# dcb_lite_logic.net
KiCad netlist of a schematic drawn in Altium Designer
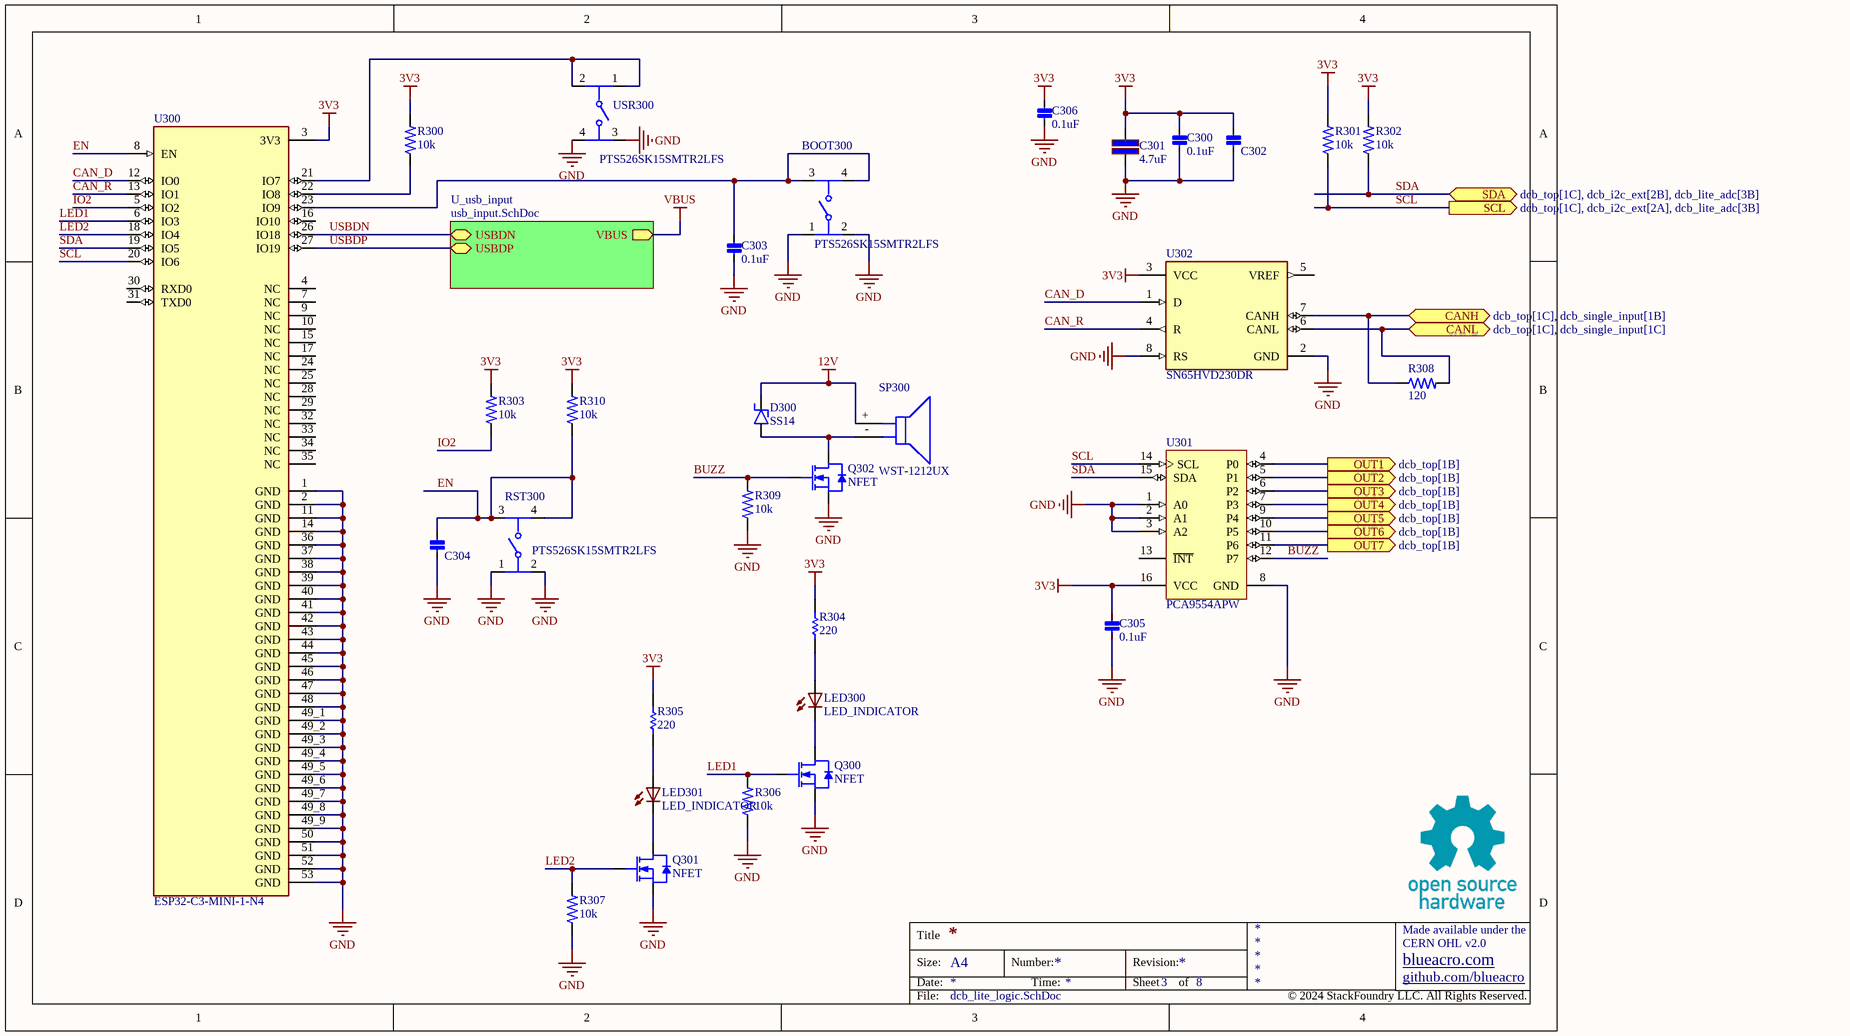
[diagram p0: dcb_lite_logic.SchDoc]

(export (version "E")
  (design (tool "Eeschema 10.0.6"))
  (components
    (comp (ref "BOOT300")
      (value "PTS526SK15SMTR2LFS")
      (footprint "FP-PTS526SK15SMTR2LFS-MFG")
      (description "Switch Tactile N.O. SPST Round Button Gull Wing 0.05A 12VDC 200000Cycles 2.45N SMD T/R")
      (libsource (lib "StackFoundry LLC") (part "b8895f3f4cefb76e1819d2863dba89b"))
    )
    (comp (ref "C300")
      (value "0.1uF")
      (footprint "FP-CL10-IPC_B")
      (description "Cap Ceramic 0.1uF 50V X7R 20% SMD 0603 125C Paper T/R")
      (fields (field (name "VOLTAGE") "50V") (field (name "Comment") "CAP 0.1uF 50V X7R 0603"))
      (libsource (lib "StackFoundry LLC") (part "C-EU"))
    )
    (comp (ref "C301")
      (value "4.7uF")
      (footprint "CAPC3225X20N")
      (description "CAP CER 4.7UF 50V X7R 1210")
      (fields (field (name "VOLTAGE") "50V") (field (name "TOLERANCE") "10%"))
      (libsource (lib "StackFoundry LLC") (part "4.7uF"))
    )
    (comp (ref "C302")
      (value "CAP 1uF 10V X7R 0603")
      (footprint "FP-CL10-IPC_B")
      (description "Cap Ceramic 1uF 10V X7R 10% SMD 0603 125C Paper T/R")
      (libsource (lib "StackFoundry LLC") (part "C-EU"))
    )
    (comp (ref "C303")
      (value "0.1uF")
      (footprint "FP-CL10-IPC_B")
      (description "Cap Ceramic 0.1uF 50V X7R 20% SMD 0603 125C Paper T/R")
      (fields (field (name "VOLTAGE") "50V") (field (name "Comment") "CAP 0.1uF 50V X7R 0603"))
      (libsource (lib "StackFoundry LLC") (part "C-EU"))
    )
    (comp (ref "C304")
      (value "CAP 1uF 10V X7R 0603")
      (footprint "FP-CL10-IPC_B")
      (description "Cap Ceramic 1uF 10V X7R 10% SMD 0603 125C Paper T/R")
      (libsource (lib "StackFoundry LLC") (part "C-EU"))
    )
    (comp (ref "C305")
      (value "0.1uF")
      (footprint "FP-CL10-IPC_B")
      (description "Cap Ceramic 0.1uF 50V X7R 20% SMD 0603 125C Paper T/R")
      (fields (field (name "VOLTAGE") "50V") (field (name "Comment") "CAP 0.1uF 50V X7R 0603"))
      (libsource (lib "StackFoundry LLC") (part "C-EU"))
    )
    (comp (ref "C306")
      (value "0.1uF")
      (footprint "FP-CL10-IPC_B")
      (description "Cap Ceramic 0.1uF 50V X7R 20% SMD 0603 125C Paper T/R")
      (fields (field (name "VOLTAGE") "50V") (field (name "Comment") "CAP 0.1uF 50V X7R 0603"))
      (libsource (lib "StackFoundry LLC") (part "C-EU"))
    )
    (comp (ref "D300")
      (value "SS14")
      (footprint "SMA")
      (libsource (lib "StackFoundry LLC") (part "DIODE_SCHOTTKY"))
    )
    (comp (ref "LED300")
      (value "LED_INDICATOR")
      (footprint "LED5MM")
      (libsource (lib "StackFoundry LLC") (part "LED_INDICATOR"))
    )
    (comp (ref "LED301")
      (value "LED_INDICATOR")
      (footprint "LED5MM")
      (libsource (lib "StackFoundry LLC") (part "LED_INDICATOR"))
    )
    (comp (ref "Q300")
      (value "NFET")
      (footprint "SOT23-3")
      (libsource (lib "StackFoundry LLC") (part "NFET"))
    )
    (comp (ref "Q301")
      (value "NFET")
      (footprint "SOT23-3")
      (libsource (lib "StackFoundry LLC") (part "NFET"))
    )
    (comp (ref "Q302")
      (value "NFET")
      (footprint "SOT23-3")
      (libsource (lib "StackFoundry LLC") (part "NFET"))
    )
    (comp (ref "R300")
      (value "10k")
      (footprint "RESC1608-IPC-ML")
      (description "Res General Purpose Thick Film 0603 10K Ohm 1% 1/10W ±100ppm/°C Molded SMD Paper T/R")
      (fields (field (name "Comment") "10K 0603 1%"))
      (libsource (lib "StackFoundry LLC") (part "R-US"))
    )
    (comp (ref "R301")
      (value "10k")
      (footprint "RESC1608-IPC-ML")
      (description "Res General Purpose Thick Film 0603 10K Ohm 1% 1/10W ±100ppm/°C Molded SMD Paper T/R")
      (fields (field (name "Comment") "10K 0603 1%"))
      (libsource (lib "StackFoundry LLC") (part "R-US"))
    )
    (comp (ref "R302")
      (value "10k")
      (footprint "RESC1608-IPC-ML")
      (description "Res General Purpose Thick Film 0603 10K Ohm 1% 1/10W ±100ppm/°C Molded SMD Paper T/R")
      (fields (field (name "Comment") "10K 0603 1%"))
      (libsource (lib "StackFoundry LLC") (part "R-US"))
    )
    (comp (ref "R303")
      (value "10k")
      (footprint "RESC1608-IPC-ML")
      (description "Res General Purpose Thick Film 0603 10K Ohm 1% 1/10W ±100ppm/°C Molded SMD Paper T/R")
      (fields (field (name "Comment") "10K 0603 1%"))
      (libsource (lib "StackFoundry LLC") (part "R-US"))
    )
    (comp (ref "R304")
      (value "220")
      (footprint "RESC1608-IPC-ML")
      (fields (field (name "TOLERANCE") "5%") (field (name "Comment") "220R 0603 5%"))
      (libsource (lib "StackFoundry LLC") (part "RES-2"))
    )
    (comp (ref "R305")
      (value "220")
      (footprint "RESC1608-IPC-ML")
      (fields (field (name "TOLERANCE") "5%") (field (name "Comment") "220R 0603 5%"))
      (libsource (lib "StackFoundry LLC") (part "RES-2"))
    )
    (comp (ref "R306")
      (value "10k")
      (footprint "RESC1608-IPC-ML")
      (description "Res General Purpose Thick Film 0603 10K Ohm 1% 1/10W ±100ppm/°C Molded SMD Paper T/R")
      (fields (field (name "Comment") "10K 0603 1%"))
      (libsource (lib "StackFoundry LLC") (part "R-US"))
    )
    (comp (ref "R307")
      (value "10k")
      (footprint "RESC1608-IPC-ML")
      (description "Res General Purpose Thick Film 0603 10K Ohm 1% 1/10W ±100ppm/°C Molded SMD Paper T/R")
      (fields (field (name "Comment") "10K 0603 1%"))
      (libsource (lib "StackFoundry LLC") (part "R-US"))
    )
    (comp (ref "R308")
      (value "120")
      (footprint "RESC1608-IPC-ML")
      (description "120R 0.1W 5% 0603 (1608 Metric)  SMD")
      (fields (field (name "TOLERANCE") "5%") (field (name "POWER") "100mW"))
      (libsource (lib "StackFoundry LLC") (part "R-US"))
    )
    (comp (ref "R309")
      (value "10k")
      (footprint "RESC1608-IPC-ML")
      (description "Res General Purpose Thick Film 0603 10K Ohm 1% 1/10W ±100ppm/°C Molded SMD Paper T/R")
      (fields (field (name "Comment") "10K 0603 1%"))
      (libsource (lib "StackFoundry LLC") (part "R-US"))
    )
    (comp (ref "R310")
      (value "10k")
      (footprint "RESC1608-IPC-ML")
      (description "Res General Purpose Thick Film 0603 10K Ohm 1% 1/10W ±100ppm/°C Molded SMD Paper T/R")
      (fields (field (name "Comment") "10K 0603 1%"))
      (libsource (lib "StackFoundry LLC") (part "R-US"))
    )
    (comp (ref "RST300")
      (value "PTS526SK15SMTR2LFS")
      (footprint "FP-PTS526SK15SMTR2LFS-MFG")
      (description "Switch Tactile N.O. SPST Round Button Gull Wing 0.05A 12VDC 200000Cycles 2.45N SMD T/R")
      (libsource (lib "StackFoundry LLC") (part "b8895f3f4cefb76e1819d2863dba89b"))
    )
    (comp (ref "SP300")
      (value "WST-1212UX")
      (footprint "WST-1212UX-Footprint-1")
      (description "Audio Magnetic Xdcr 9-15V Th")
      (libsource (lib "StackFoundry LLC") (part "WST-1212UX-Symbol-1"))
    )
    (comp (ref "U300")
      (value "ESP32-C3-MINI-1-N4")
      (footprint "XCVR_ESP32-C3-MINI-1-N4")
      (fields (field (name "MF") "Espressif Systems"))
      (libsource (lib "StackFoundry LLC") (part "ESP32-C3-MINI-1-N4"))
    )
    (comp (ref "U301")
      (value "PCA9554APW")
      (footprint "PW0016A_L")
      (description "I2C/SMBus Interface 100kHz/400kHz 5.5V 16-Pin TSSOP Tube / IC I/O EXPANDER I2C 8B 16TSSOP")
      (libsource (lib "StackFoundry LLC") (part "TI-PCA9554A-TSSOP_PW-16"))
    )
    (comp (ref "U302")
      (value "SN65HVD230DR")
      (footprint "FP-D0008A-IPC_B")
      (description "EAR99 65HVD230 Cut Tape (CT) CANbus interface driver 3.3V 17mA 72.603129mg 1Mbps")
      (libsource (lib "StackFoundry LLC") (part "43b56812b1adf0e60a7acfb7c27ab91"))
    )
    (comp (ref "USR300")
      (value "PTS526SK15SMTR2LFS")
      (footprint "FP-PTS526SK15SMTR2LFS-MFG")
      (description "Switch Tactile N.O. SPST Round Button Gull Wing 0.05A 12VDC 200000Cycles 2.45N SMD T/R")
      (libsource (lib "StackFoundry LLC") (part "b8895f3f4cefb76e1819d2863dba89b"))
    )
  )
  (nets
    (net (code "1") (name "/BUZZ") (class "Default")
      (node (ref "Q302") (pin "1") (pinfunction "G_1") (pintype "passive"))
      (node (ref "R309") (pin "2") (pinfunction "2_2") (pintype "passive"))
      (node (ref "U301") (pin "12") (pinfunction "P7_12") (pintype "bidirectional"))
    )
    (net (code "2") (name "/CANH") (class "Default")
      (node (ref "R308") (pin "1") (pinfunction "1_1") (pintype "passive"))
      (node (ref "U302") (pin "7") (pinfunction "CANH_7") (pintype "bidirectional"))
    )
    (net (code "3") (name "/CANL") (class "Default")
      (node (ref "R308") (pin "2") (pinfunction "2_2") (pintype "passive"))
      (node (ref "U302") (pin "6") (pinfunction "CANL_6") (pintype "bidirectional"))
    )
    (net (code "4") (name "/CAN_D") (class "Default")
      (node (ref "U300") (pin "12") (pinfunction "IO0_12") (pintype "bidirectional"))
      (node (ref "U302") (pin "1") (pinfunction "D_1") (pintype "input"))
    )
    (net (code "5") (name "/CAN_R") (class "Default")
      (node (ref "U300") (pin "13") (pinfunction "IO1_13") (pintype "bidirectional"))
      (node (ref "U302") (pin "4") (pinfunction "R_4") (pintype "output"))
    )
    (net (code "6") (name "/EN") (class "Default")
      (node (ref "C304") (pin "1") (pinfunction "1_1") (pintype "passive"))
      (node (ref "R310") (pin "1") (pinfunction "1_1") (pintype "passive"))
      (node (ref "RST300") (pin "3") (pinfunction "3_3") (pintype "passive"))
      (node (ref "RST300") (pin "4") (pinfunction "4_4") (pintype "passive"))
      (node (ref "U300") (pin "8") (pinfunction "EN_8") (pintype "input"))
    )
    (net (code "7") (name "/IO2") (class "Default")
      (node (ref "R303") (pin "1") (pinfunction "1_1") (pintype "passive"))
      (node (ref "U300") (pin "5") (pinfunction "IO2_5") (pintype "bidirectional"))
    )
    (net (code "8") (name "/LED1") (class "Default")
      (node (ref "Q300") (pin "1") (pinfunction "G_1") (pintype "passive"))
      (node (ref "R306") (pin "2") (pinfunction "2_2") (pintype "passive"))
      (node (ref "U300") (pin "6") (pinfunction "IO3_6") (pintype "bidirectional"))
    )
    (net (code "9") (name "/LED2") (class "Default")
      (node (ref "Q301") (pin "1") (pinfunction "G_1") (pintype "passive"))
      (node (ref "R307") (pin "2") (pinfunction "2_2") (pintype "passive"))
      (node (ref "U300") (pin "18") (pinfunction "IO4_18") (pintype "bidirectional"))
    )
    (net (code "10") (name "/OUT1") (class "Default")
      (node (ref "U301") (pin "4") (pinfunction "P0_4") (pintype "bidirectional"))
    )
    (net (code "11") (name "/OUT2") (class "Default")
      (node (ref "U301") (pin "5") (pinfunction "P1_5") (pintype "bidirectional"))
    )
    (net (code "12") (name "/OUT3") (class "Default")
      (node (ref "U301") (pin "6") (pinfunction "P2_6") (pintype "bidirectional"))
    )
    (net (code "13") (name "/OUT4") (class "Default")
      (node (ref "U301") (pin "7") (pinfunction "P3_7") (pintype "bidirectional"))
    )
    (net (code "14") (name "/OUT5") (class "Default")
      (node (ref "U301") (pin "9") (pinfunction "P4_9") (pintype "bidirectional"))
    )
    (net (code "15") (name "/OUT6") (class "Default")
      (node (ref "U301") (pin "10") (pinfunction "P5_10") (pintype "bidirectional"))
    )
    (net (code "16") (name "/OUT7") (class "Default")
      (node (ref "U301") (pin "11") (pinfunction "P6_11") (pintype "bidirectional"))
    )
    (net (code "17") (name "/SCL") (class "Default")
      (node (ref "R301") (pin "1") (pinfunction "1_1") (pintype "passive"))
      (node (ref "U300") (pin "20") (pinfunction "IO6_20") (pintype "bidirectional"))
      (node (ref "U301") (pin "14") (pinfunction "SCL_14") (pintype "input"))
    )
    (net (code "18") (name "/SDA") (class "Default")
      (node (ref "R302") (pin "1") (pinfunction "1_1") (pintype "passive"))
      (node (ref "U300") (pin "19") (pinfunction "IO5_19") (pintype "bidirectional"))
      (node (ref "U301") (pin "15") (pinfunction "SDA_15") (pintype "bidirectional"))
    )
    (net (code "19") (name "/USBDN") (class "Default")
      (node (ref "U300") (pin "26") (pinfunction "IO18_26") (pintype "bidirectional"))
    )
    (net (code "20") (name "/USBDP") (class "Default")
      (node (ref "U300") (pin "27") (pinfunction "IO19_27") (pintype "bidirectional"))
    )
    (net (code "21") (name "3V3") (class "Default")
      (node (ref "C300") (pin "1") (pinfunction "1_1") (pintype "passive"))
      (node (ref "C301") (pin "2") (pintype "passive"))
      (node (ref "C302") (pin "1") (pinfunction "1_1") (pintype "passive"))
      (node (ref "C305") (pin "1") (pinfunction "1_1") (pintype "passive"))
      (node (ref "C306") (pin "1") (pinfunction "1_1") (pintype "passive"))
      (node (ref "R300") (pin "2") (pinfunction "2_2") (pintype "passive"))
      (node (ref "R301") (pin "2") (pinfunction "2_2") (pintype "passive"))
      (node (ref "R302") (pin "2") (pinfunction "2_2") (pintype "passive"))
      (node (ref "R303") (pin "2") (pinfunction "2_2") (pintype "passive"))
      (node (ref "R304") (pin "2") (pinfunction "2_2") (pintype "passive"))
      (node (ref "R305") (pin "2") (pinfunction "2_2") (pintype "passive"))
      (node (ref "R310") (pin "2") (pinfunction "2_2") (pintype "passive"))
      (node (ref "U300") (pin "3") (pinfunction "3V3_3") (pintype "power_in"))
      (node (ref "U301") (pin "16") (pinfunction "VCC_16") (pintype "power_in"))
      (node (ref "U302") (pin "3") (pinfunction "VCC_3") (pintype "power_in"))
    )
    (net (code "22") (name "12V") (class "Default")
      (node (ref "D300") (pin "K") (pinfunction "K_K") (pintype "power_in"))
      (node (ref "SP300") (pin "+") (pinfunction "+_+") (pintype "passive"))
    )
    (net (code "23") (name "GND") (class "Default")
      (node (ref "BOOT300") (pin "1") (pinfunction "1_1") (pintype "passive"))
      (node (ref "BOOT300") (pin "2") (pinfunction "2_2") (pintype "passive"))
      (node (ref "C300") (pin "2") (pinfunction "2_2") (pintype "passive"))
      (node (ref "C301") (pin "1") (pintype "passive"))
      (node (ref "C302") (pin "2") (pinfunction "2_2") (pintype "passive"))
      (node (ref "C303") (pin "2") (pinfunction "2_2") (pintype "passive"))
      (node (ref "C304") (pin "2") (pinfunction "2_2") (pintype "passive"))
      (node (ref "C305") (pin "2") (pinfunction "2_2") (pintype "passive"))
      (node (ref "C306") (pin "2") (pinfunction "2_2") (pintype "passive"))
      (node (ref "Q300") (pin "2") (pinfunction "S_2") (pintype "passive"))
      (node (ref "Q301") (pin "2") (pinfunction "S_2") (pintype "passive"))
      (node (ref "Q302") (pin "2") (pinfunction "S_2") (pintype "passive"))
      (node (ref "R306") (pin "1") (pinfunction "1_1") (pintype "passive"))
      (node (ref "R307") (pin "1") (pinfunction "1_1") (pintype "passive"))
      (node (ref "R309") (pin "1") (pinfunction "1_1") (pintype "passive"))
      (node (ref "RST300") (pin "1") (pinfunction "1_1") (pintype "passive"))
      (node (ref "RST300") (pin "2") (pinfunction "2_2") (pintype "passive"))
      (node (ref "U300") (pin "1") (pinfunction "GND_1") (pintype "power_in"))
      (node (ref "U300") (pin "11") (pinfunction "GND_11") (pintype "power_in"))
      (node (ref "U300") (pin "14") (pinfunction "GND_14") (pintype "power_in"))
      (node (ref "U300") (pin "2") (pinfunction "GND_2") (pintype "power_in"))
      (node (ref "U300") (pin "36") (pinfunction "GND_36") (pintype "power_in"))
      (node (ref "U300") (pin "37") (pinfunction "GND_37") (pintype "power_in"))
      (node (ref "U300") (pin "38") (pinfunction "GND_38") (pintype "power_in"))
      (node (ref "U300") (pin "39") (pinfunction "GND_39") (pintype "power_in"))
      (node (ref "U300") (pin "40") (pinfunction "GND_40") (pintype "power_in"))
      (node (ref "U300") (pin "41") (pinfunction "GND_41") (pintype "power_in"))
      (node (ref "U300") (pin "42") (pinfunction "GND_42") (pintype "power_in"))
      (node (ref "U300") (pin "43") (pinfunction "GND_43") (pintype "power_in"))
      (node (ref "U300") (pin "44") (pinfunction "GND_44") (pintype "power_in"))
      (node (ref "U300") (pin "45") (pinfunction "GND_45") (pintype "power_in"))
      (node (ref "U300") (pin "46") (pinfunction "GND_46") (pintype "power_in"))
      (node (ref "U300") (pin "47") (pinfunction "GND_47") (pintype "power_in"))
      (node (ref "U300") (pin "48") (pinfunction "GND_48") (pintype "power_in"))
      (node (ref "U300") (pin "49_1") (pinfunction "GND_49_1") (pintype "power_in"))
      (node (ref "U300") (pin "49_2") (pinfunction "GND_49_2") (pintype "power_in"))
      (node (ref "U300") (pin "49_3") (pinfunction "GND_49_3") (pintype "power_in"))
      (node (ref "U300") (pin "49_4") (pinfunction "GND_49_4") (pintype "power_in"))
      (node (ref "U300") (pin "49_5") (pinfunction "GND_49_5") (pintype "power_in"))
      (node (ref "U300") (pin "49_6") (pinfunction "GND_49_6") (pintype "power_in"))
      (node (ref "U300") (pin "49_7") (pinfunction "GND_49_7") (pintype "power_in"))
      (node (ref "U300") (pin "49_8") (pinfunction "GND_49_8") (pintype "power_in"))
      (node (ref "U300") (pin "49_9") (pinfunction "GND_49_9") (pintype "power_in"))
      (node (ref "U300") (pin "50") (pinfunction "GND_50") (pintype "power_in"))
      (node (ref "U300") (pin "51") (pinfunction "GND_51") (pintype "power_in"))
      (node (ref "U300") (pin "52") (pinfunction "GND_52") (pintype "power_in"))
      (node (ref "U300") (pin "53") (pinfunction "GND_53") (pintype "power_in"))
      (node (ref "U301") (pin "1") (pinfunction "A0_1") (pintype "input"))
      (node (ref "U301") (pin "2") (pinfunction "A1_2") (pintype "input"))
      (node (ref "U301") (pin "3") (pinfunction "A2_3") (pintype "input"))
      (node (ref "U301") (pin "8") (pinfunction "GND_8") (pintype "power_in"))
      (node (ref "U302") (pin "2") (pinfunction "GND_2") (pintype "power_in"))
      (node (ref "U302") (pin "8") (pinfunction "RS_8") (pintype "input"))
      (node (ref "USR300") (pin "3") (pinfunction "3_3") (pintype "passive"))
      (node (ref "USR300") (pin "4") (pinfunction "4_4") (pintype "passive"))
    )
    (net (code "24") (name "Net-(LED300-PadA)") (class "Default")
      (node (ref "LED300") (pin "A") (pinfunction "A_A") (pintype "passive"))
      (node (ref "R304") (pin "1") (pinfunction "1_1") (pintype "passive"))
    )
    (net (code "25") (name "Net-(LED301-PadA)") (class "Default")
      (node (ref "LED301") (pin "A") (pinfunction "A_A") (pintype "passive"))
      (node (ref "R305") (pin "1") (pinfunction "1_1") (pintype "passive"))
    )
    (net (code "26") (name "Net-(Q300-D)") (class "Default")
      (node (ref "LED300") (pin "C") (pinfunction "C_C") (pintype "passive"))
      (node (ref "Q300") (pin "3") (pinfunction "D_3") (pintype "passive"))
    )
    (net (code "27") (name "Net-(Q301-D)") (class "Default")
      (node (ref "LED301") (pin "C") (pinfunction "C_C") (pintype "passive"))
      (node (ref "Q301") (pin "3") (pinfunction "D_3") (pintype "passive"))
    )
    (net (code "28") (name "Net-(Q302-D)") (class "Default")
      (node (ref "D300") (pin "A") (pinfunction "A_A") (pintype "power_in"))
      (node (ref "Q302") (pin "3") (pinfunction "D_3") (pintype "passive"))
      (node (ref "SP300") (pin "-") (pinfunction "-_-") (pintype "passive"))
    )
    (net (code "29") (name "Net-(U300-IO7)") (class "Default")
      (node (ref "U300") (pin "21") (pinfunction "IO7_21") (pintype "bidirectional"))
      (node (ref "USR300") (pin "1") (pinfunction "1_1") (pintype "passive"))
      (node (ref "USR300") (pin "2") (pinfunction "2_2") (pintype "passive"))
    )
    (net (code "30") (name "Net-(U300-IO8)") (class "Default")
      (node (ref "R300") (pin "1") (pinfunction "1_1") (pintype "passive"))
      (node (ref "U300") (pin "22") (pinfunction "IO8_22") (pintype "bidirectional"))
    )
    (net (code "31") (name "Net-(U300-IO9)") (class "Default")
      (node (ref "BOOT300") (pin "3") (pinfunction "3_3") (pintype "passive"))
      (node (ref "BOOT300") (pin "4") (pinfunction "4_4") (pintype "passive"))
      (node (ref "C303") (pin "1") (pinfunction "1_1") (pintype "passive"))
      (node (ref "U300") (pin "23") (pinfunction "IO9_23") (pintype "bidirectional"))
    )
    (net (code "33") (name "unconnected-(U300-IO10-Pad16)") (class "Default")
      (node (ref "U300") (pin "16") (pinfunction "IO10_16") (pintype "bidirectional"))
    )
    (net (code "34") (name "unconnected-(U300-NC-Pad4)") (class "Default")
      (node (ref "U300") (pin "4") (pinfunction "NC_4") (pintype "passive"))
    )
    (net (code "35") (name "unconnected-(U300-NC-Pad7)") (class "Default")
      (node (ref "U300") (pin "7") (pinfunction "NC_7") (pintype "passive"))
    )
    (net (code "36") (name "unconnected-(U300-NC-Pad9)") (class "Default")
      (node (ref "U300") (pin "9") (pinfunction "NC_9") (pintype "passive"))
    )
    (net (code "37") (name "unconnected-(U300-NC-Pad10)") (class "Default")
      (node (ref "U300") (pin "10") (pinfunction "NC_10") (pintype "passive"))
    )
    (net (code "38") (name "unconnected-(U300-NC-Pad15)") (class "Default")
      (node (ref "U300") (pin "15") (pinfunction "NC_15") (pintype "passive"))
    )
    (net (code "39") (name "unconnected-(U300-NC-Pad17)") (class "Default")
      (node (ref "U300") (pin "17") (pinfunction "NC_17") (pintype "passive"))
    )
    (net (code "40") (name "unconnected-(U300-NC-Pad24)") (class "Default")
      (node (ref "U300") (pin "24") (pinfunction "NC_24") (pintype "passive"))
    )
    (net (code "41") (name "unconnected-(U300-NC-Pad25)") (class "Default")
      (node (ref "U300") (pin "25") (pinfunction "NC_25") (pintype "passive"))
    )
    (net (code "42") (name "unconnected-(U300-NC-Pad28)") (class "Default")
      (node (ref "U300") (pin "28") (pinfunction "NC_28") (pintype "passive"))
    )
    (net (code "43") (name "unconnected-(U300-NC-Pad29)") (class "Default")
      (node (ref "U300") (pin "29") (pinfunction "NC_29") (pintype "passive"))
    )
    (net (code "44") (name "unconnected-(U300-NC-Pad32)") (class "Default")
      (node (ref "U300") (pin "32") (pinfunction "NC_32") (pintype "passive"))
    )
    (net (code "45") (name "unconnected-(U300-NC-Pad33)") (class "Default")
      (node (ref "U300") (pin "33") (pinfunction "NC_33") (pintype "passive"))
    )
    (net (code "46") (name "unconnected-(U300-NC-Pad34)") (class "Default")
      (node (ref "U300") (pin "34") (pinfunction "NC_34") (pintype "passive"))
    )
    (net (code "47") (name "unconnected-(U300-NC-Pad35)") (class "Default")
      (node (ref "U300") (pin "35") (pinfunction "NC_35") (pintype "passive"))
    )
    (net (code "48") (name "unconnected-(U300-RXD0-Pad30)") (class "Default")
      (node (ref "U300") (pin "30") (pinfunction "RXD0_30") (pintype "bidirectional"))
    )
    (net (code "49") (name "unconnected-(U300-TXD0-Pad31)") (class "Default")
      (node (ref "U300") (pin "31") (pinfunction "TXD0_31") (pintype "bidirectional"))
    )
    (net (code "50") (name "unconnected-(U301-~{INT}-Pad13)") (class "Default")
      (node (ref "U301") (pin "13") (pinfunction "~{INT}_13") (pintype "open_collector"))
    )
    (net (code "51") (name "unconnected-(U302-VREF-Pad5)") (class "Default")
      (node (ref "U302") (pin "5") (pinfunction "VREF_5") (pintype "output"))
    )
  )
)
